# EEPROM.net
KiCad netlist of a schematic drawn in Altium Designer
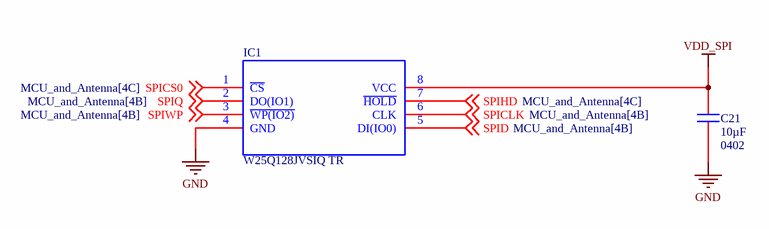
[diagram p0: EEPROM.SchDoc]

(export (version "E")
  (design (tool "Eeschema 10.0.6"))
  (components
    (comp (ref "C21")
      (value "10µF")
      (footprint "CAPC1005X55N")
      (description "6.3V 10uF X5R ±20% 0402 Multilayer Ceramic Capacitors MLCC - SMD/SMT ROHS")
      (fields
        (field (name "MANUFACTURER") "Murata")
        (field (name "MANUFACTURER PART NUMBER") "GRM155R60J106ME15D")
        (field (name "CASE/PACKAGE") "0402")
      )
      (libsource (lib "Schlib") (part "GRM155R60J106ME15D"))
    )
    (comp (ref "IC1")
      (value "W25Q128JVSIQ TR")
      (footprint "SOIC_208MIL_WIN-M")
      (description "NOR Flash Serial (SPI, Dual SPI, Quad SPI) 3V/3.3V 128M-bit 16M x 8 6ns 8-Pin SOIC T/R")
      (fields (field (name "MANUFACTURER") "Winbond") (field (name "LCSC PART") "C97521"))
      (libsource (lib "Schlib") (part "W25Q128JVSIQ TR"))
    )
  )
  (nets
    (net (code "1") (name "GND") (class "Default")
      (node (ref "C21") (pin "1") (pinfunction "1_1") (pintype "passive"))
      (node (ref "IC1") (pin "4") (pinfunction "GND_4") (pintype "passive"))
    )
    (net (code "2") (name "SPICLK") (class "Default")
      (node (ref "IC1") (pin "6") (pinfunction "CLK_6") (pintype "passive"))
    )
    (net (code "3") (name "SPICS0") (class "Default")
      (node (ref "IC1") (pin "1") (pinfunction "~{CS}_1") (pintype "passive"))
    )
    (net (code "4") (name "SPID") (class "Default")
      (node (ref "IC1") (pin "5") (pinfunction "DI(IO0)_5") (pintype "passive"))
    )
    (net (code "5") (name "SPIHD") (class "Default")
      (node (ref "IC1") (pin "7") (pinfunction "~{HOLD}_7") (pintype "passive"))
    )
    (net (code "6") (name "SPIQ") (class "Default")
      (node (ref "IC1") (pin "2") (pinfunction "DO(IO1)_2") (pintype "passive"))
    )
    (net (code "7") (name "SPIWP") (class "Default")
      (node (ref "IC1") (pin "3") (pinfunction "~{WP(IO2)}_3") (pintype "passive"))
    )
    (net (code "8") (name "VDD_SPI") (class "Default")
      (node (ref "C21") (pin "2") (pinfunction "2_2") (pintype "passive"))
      (node (ref "IC1") (pin "8") (pinfunction "VCC_8") (pintype "passive"))
    )
  )
)
